# imu-adapter.net
KiCad netlist of a schematic drawn in EAGLE
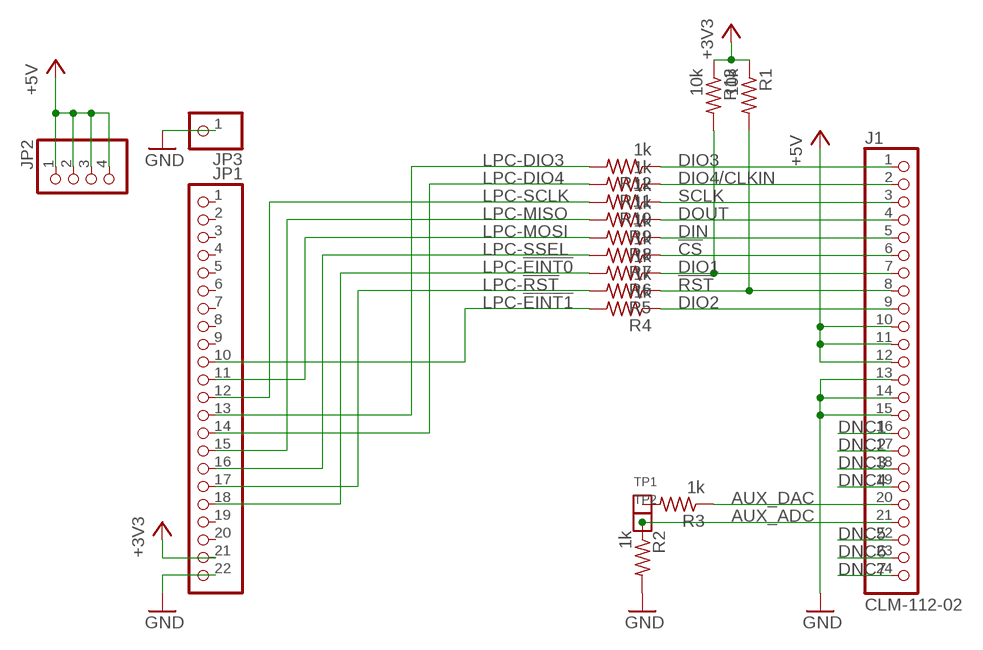
[diagram p0: schematic, sheet 1]

(export (version "E")
  (design (tool "Eeschema 10.0.6"))
  (components
    (comp (ref "J1")
      (value "CLM-112-02")
      (footprint "eagle-import:CLM-112-02-XX-D-A")
      (libsource (lib "eagle-import") (part "CLM-112-02"))
    )
    (comp (ref "JP1")
      (value "PINHD-1X22")
      (footprint "eagle-import:1X22")
      (libsource (lib "eagle-import") (part "PINHD-1X22"))
    )
    (comp (ref "JP2")
      (value "PINHD-1X4")
      (footprint "eagle-import:1X04")
      (libsource (lib "eagle-import") (part "PINHD-1X4"))
    )
    (comp (ref "JP3")
      (value "PINHD-1X1")
      (footprint "eagle-import:1X01")
      (libsource (lib "eagle-import") (part "PINHD-1X1"))
    )
    (comp (ref "R1")
      (value "10k")
      (footprint "eagle-import:0603-B-NOSILK")
      (libsource (lib "eagle-import") (part "R-US_0603-B-NOSILK"))
    )
    (comp (ref "R2")
      (value "1k")
      (footprint "eagle-import:0603-B-NOSILK")
      (libsource (lib "eagle-import") (part "R-US_0603-B-NOSILK"))
    )
    (comp (ref "R3")
      (value "1k")
      (footprint "eagle-import:0603-B-NOSILK")
      (libsource (lib "eagle-import") (part "R-US_0603-B-NOSILK"))
    )
    (comp (ref "R4")
      (value "1k")
      (footprint "eagle-import:0603-B-NOSILK")
      (libsource (lib "eagle-import") (part "R-US_0603-B-NOSILK"))
    )
    (comp (ref "R5")
      (value "1k")
      (footprint "eagle-import:0603-B-NOSILK")
      (libsource (lib "eagle-import") (part "R-US_0603-B-NOSILK"))
    )
    (comp (ref "R6")
      (value "1k")
      (footprint "eagle-import:0603-B-NOSILK")
      (libsource (lib "eagle-import") (part "R-US_0603-B-NOSILK"))
    )
    (comp (ref "R7")
      (value "1k")
      (footprint "eagle-import:0603-B-NOSILK")
      (libsource (lib "eagle-import") (part "R-US_0603-B-NOSILK"))
    )
    (comp (ref "R8")
      (value "1k")
      (footprint "eagle-import:0603-B-NOSILK")
      (libsource (lib "eagle-import") (part "R-US_0603-B-NOSILK"))
    )
    (comp (ref "R9")
      (value "1k")
      (footprint "eagle-import:0603-B-NOSILK")
      (libsource (lib "eagle-import") (part "R-US_0603-B-NOSILK"))
    )
    (comp (ref "R10")
      (value "1k")
      (footprint "eagle-import:0603-B-NOSILK")
      (libsource (lib "eagle-import") (part "R-US_0603-B-NOSILK"))
    )
    (comp (ref "R11")
      (value "1k")
      (footprint "eagle-import:0603-B-NOSILK")
      (libsource (lib "eagle-import") (part "R-US_0603-B-NOSILK"))
    )
    (comp (ref "R12")
      (value "1k")
      (footprint "eagle-import:0603-B-NOSILK")
      (libsource (lib "eagle-import") (part "R-US_0603-B-NOSILK"))
    )
    (comp (ref "R13")
      (value "10k")
      (footprint "eagle-import:0603-B-NOSILK")
      (libsource (lib "eagle-import") (part "R-US_0603-B-NOSILK"))
    )
    (comp (ref "TP1")
      (value "TEST-POINT")
      (footprint "eagle-import:2MM-TEST-POINT")
      (libsource (lib "eagle-import") (part "TEST-POINT"))
    )
    (comp (ref "TP2")
      (value "TEST-POINT")
      (footprint "eagle-import:2MM-TEST-POINT")
      (libsource (lib "eagle-import") (part "TEST-POINT"))
    )
  )
  (nets
    (net (code "1") (name "+3V3") (class "Default")
      (node (ref "JP1") (pin "21") (pinfunction "21_21") (pintype "passive"))
      (node (ref "R1") (pin "1") (pinfunction "1_1") (pintype "passive"))
      (node (ref "R13") (pin "1") (pinfunction "1_1") (pintype "passive"))
    )
    (net (code "2") (name "+5V") (class "Default")
      (node (ref "J1") (pin "10") (pinfunction "10_10") (pintype "passive"))
      (node (ref "J1") (pin "11") (pinfunction "11_11") (pintype "passive"))
      (node (ref "J1") (pin "12") (pinfunction "12_12") (pintype "passive"))
      (node (ref "JP2") (pin "1") (pinfunction "1_1") (pintype "passive"))
      (node (ref "JP2") (pin "2") (pinfunction "2_2") (pintype "passive"))
      (node (ref "JP2") (pin "3") (pinfunction "3_3") (pintype "passive"))
      (node (ref "JP2") (pin "4") (pinfunction "4_4") (pintype "passive"))
    )
    (net (code "3") (name "/AUX_ADC") (class "Default")
      (node (ref "J1") (pin "21") (pinfunction "21_21") (pintype "passive"))
      (node (ref "R2") (pin "1") (pinfunction "1_1") (pintype "passive"))
      (node (ref "TP2") (pin "1") (pinfunction "P$1_1") (pintype "passive"))
    )
    (net (code "4") (name "/AUX_DAC") (class "Default")
      (node (ref "J1") (pin "20") (pinfunction "20_20") (pintype "passive"))
      (node (ref "R3") (pin "1") (pinfunction "1_1") (pintype "passive"))
    )
    (net (code "5") (name "/DIN") (class "Default")
      (node (ref "J1") (pin "5") (pinfunction "5_5") (pintype "passive"))
      (node (ref "R8") (pin "1") (pinfunction "1_1") (pintype "passive"))
    )
    (net (code "6") (name "/DIO1") (class "Default")
      (node (ref "J1") (pin "7") (pinfunction "7_7") (pintype "passive"))
      (node (ref "R13") (pin "2") (pinfunction "2_2") (pintype "passive"))
      (node (ref "R6") (pin "1") (pinfunction "1_1") (pintype "passive"))
    )
    (net (code "7") (name "/DIO2") (class "Default")
      (node (ref "J1") (pin "9") (pinfunction "9_9") (pintype "passive"))
      (node (ref "R4") (pin "1") (pinfunction "1_1") (pintype "passive"))
    )
    (net (code "8") (name "/DIO3") (class "Default")
      (node (ref "J1") (pin "1") (pinfunction "1_1") (pintype "passive"))
      (node (ref "R12") (pin "1") (pinfunction "1_1") (pintype "passive"))
    )
    (net (code "9") (name "/DIO4{slash}CLKIN") (class "Default")
      (node (ref "J1") (pin "2") (pinfunction "2_2") (pintype "passive"))
      (node (ref "R11") (pin "1") (pinfunction "1_1") (pintype "passive"))
    )
    (net (code "10") (name "/DNC1") (class "Default")
      (node (ref "J1") (pin "16") (pinfunction "16_16") (pintype "passive"))
    )
    (net (code "11") (name "/DNC2") (class "Default")
      (node (ref "J1") (pin "17") (pinfunction "17_17") (pintype "passive"))
    )
    (net (code "12") (name "/DNC3") (class "Default")
      (node (ref "J1") (pin "18") (pinfunction "18_18") (pintype "passive"))
    )
    (net (code "13") (name "/DNC4") (class "Default")
      (node (ref "J1") (pin "19") (pinfunction "19_19") (pintype "passive"))
    )
    (net (code "14") (name "/DNC5") (class "Default")
      (node (ref "J1") (pin "22") (pinfunction "22_22") (pintype "passive"))
    )
    (net (code "15") (name "/DNC6") (class "Default")
      (node (ref "J1") (pin "23") (pinfunction "23_23") (pintype "passive"))
    )
    (net (code "16") (name "/DNC7") (class "Default")
      (node (ref "J1") (pin "24") (pinfunction "24_24") (pintype "passive"))
    )
    (net (code "17") (name "/DOUT") (class "Default")
      (node (ref "J1") (pin "4") (pinfunction "4_4") (pintype "passive"))
      (node (ref "R9") (pin "1") (pinfunction "1_1") (pintype "passive"))
    )
    (net (code "18") (name "/LPC-DIO3") (class "Default")
      (node (ref "JP1") (pin "13") (pinfunction "13_13") (pintype "passive"))
      (node (ref "R12") (pin "2") (pinfunction "2_2") (pintype "passive"))
    )
    (net (code "19") (name "/LPC-DIO4") (class "Default")
      (node (ref "JP1") (pin "14") (pinfunction "14_14") (pintype "passive"))
      (node (ref "R11") (pin "2") (pinfunction "2_2") (pintype "passive"))
    )
    (net (code "20") (name "/LPC-MISO") (class "Default")
      (node (ref "JP1") (pin "15") (pinfunction "15_15") (pintype "passive"))
      (node (ref "R9") (pin "2") (pinfunction "2_2") (pintype "passive"))
    )
    (net (code "21") (name "/LPC-MOSI") (class "Default")
      (node (ref "JP1") (pin "11") (pinfunction "11_11") (pintype "passive"))
      (node (ref "R8") (pin "2") (pinfunction "2_2") (pintype "passive"))
    )
    (net (code "22") (name "/LPC-SCLK") (class "Default")
      (node (ref "JP1") (pin "12") (pinfunction "12_12") (pintype "passive"))
      (node (ref "R10") (pin "2") (pinfunction "2_2") (pintype "passive"))
    )
    (net (code "23") (name "/LPC-SSEL") (class "Default")
      (node (ref "JP1") (pin "16") (pinfunction "16_16") (pintype "passive"))
      (node (ref "R7") (pin "2") (pinfunction "2_2") (pintype "passive"))
    )
    (net (code "24") (name "/LPC-~{EINT0}") (class "Default")
      (node (ref "JP1") (pin "18") (pinfunction "18_18") (pintype "passive"))
      (node (ref "R6") (pin "2") (pinfunction "2_2") (pintype "passive"))
    )
    (net (code "25") (name "/LPC-~{EINT1}") (class "Default")
      (node (ref "JP1") (pin "10") (pinfunction "10_10") (pintype "passive"))
      (node (ref "R4") (pin "2") (pinfunction "2_2") (pintype "passive"))
    )
    (net (code "26") (name "/LPC-~{RST}") (class "Default")
      (node (ref "JP1") (pin "17") (pinfunction "17_17") (pintype "passive"))
      (node (ref "R5") (pin "2") (pinfunction "2_2") (pintype "passive"))
    )
    (net (code "27") (name "/SCLK") (class "Default")
      (node (ref "J1") (pin "3") (pinfunction "3_3") (pintype "passive"))
      (node (ref "R10") (pin "1") (pinfunction "1_1") (pintype "passive"))
    )
    (net (code "28") (name "/~{CS}") (class "Default")
      (node (ref "J1") (pin "6") (pinfunction "6_6") (pintype "passive"))
      (node (ref "R7") (pin "1") (pinfunction "1_1") (pintype "passive"))
    )
    (net (code "29") (name "/~{RST}") (class "Default")
      (node (ref "J1") (pin "8") (pinfunction "8_8") (pintype "passive"))
      (node (ref "R1") (pin "2") (pinfunction "2_2") (pintype "passive"))
      (node (ref "R5") (pin "1") (pinfunction "1_1") (pintype "passive"))
    )
    (net (code "30") (name "GND") (class "Default")
      (node (ref "J1") (pin "13") (pinfunction "13_13") (pintype "passive"))
      (node (ref "J1") (pin "14") (pinfunction "14_14") (pintype "passive"))
      (node (ref "J1") (pin "15") (pinfunction "15_15") (pintype "passive"))
      (node (ref "JP1") (pin "22") (pinfunction "22_22") (pintype "passive"))
      (node (ref "JP3") (pin "1") (pinfunction "1_1") (pintype "passive"))
      (node (ref "R2") (pin "2") (pinfunction "2_2") (pintype "passive"))
    )
    (net (code "31") (name "Net-(TP1-P$1)") (class "Default")
      (node (ref "R3") (pin "2") (pinfunction "2_2") (pintype "passive"))
      (node (ref "TP1") (pin "1") (pinfunction "P$1_1") (pintype "passive"))
    )
    (net (code "32") (name "unconnected-(JP1-Pad1)") (class "Default")
      (node (ref "JP1") (pin "1") (pinfunction "1_1") (pintype "passive"))
    )
    (net (code "33") (name "unconnected-(JP1-Pad2)") (class "Default")
      (node (ref "JP1") (pin "2") (pinfunction "2_2") (pintype "passive"))
    )
    (net (code "34") (name "unconnected-(JP1-Pad3)") (class "Default")
      (node (ref "JP1") (pin "3") (pinfunction "3_3") (pintype "passive"))
    )
    (net (code "35") (name "unconnected-(JP1-Pad4)") (class "Default")
      (node (ref "JP1") (pin "4") (pinfunction "4_4") (pintype "passive"))
    )
    (net (code "36") (name "unconnected-(JP1-Pad5)") (class "Default")
      (node (ref "JP1") (pin "5") (pinfunction "5_5") (pintype "passive"))
    )
    (net (code "37") (name "unconnected-(JP1-Pad6)") (class "Default")
      (node (ref "JP1") (pin "6") (pinfunction "6_6") (pintype "passive"))
    )
    (net (code "38") (name "unconnected-(JP1-Pad7)") (class "Default")
      (node (ref "JP1") (pin "7") (pinfunction "7_7") (pintype "passive"))
    )
    (net (code "39") (name "unconnected-(JP1-Pad8)") (class "Default")
      (node (ref "JP1") (pin "8") (pinfunction "8_8") (pintype "passive"))
    )
    (net (code "40") (name "unconnected-(JP1-Pad9)") (class "Default")
      (node (ref "JP1") (pin "9") (pinfunction "9_9") (pintype "passive"))
    )
    (net (code "41") (name "unconnected-(JP1-Pad19)") (class "Default")
      (node (ref "JP1") (pin "19") (pinfunction "19_19") (pintype "passive"))
    )
    (net (code "42") (name "unconnected-(JP1-Pad20)") (class "Default")
      (node (ref "JP1") (pin "20") (pinfunction "20_20") (pintype "passive"))
    )
  )
)
